# rf_front_lf.net
KiCad netlist of a schematic drawn in EAGLE
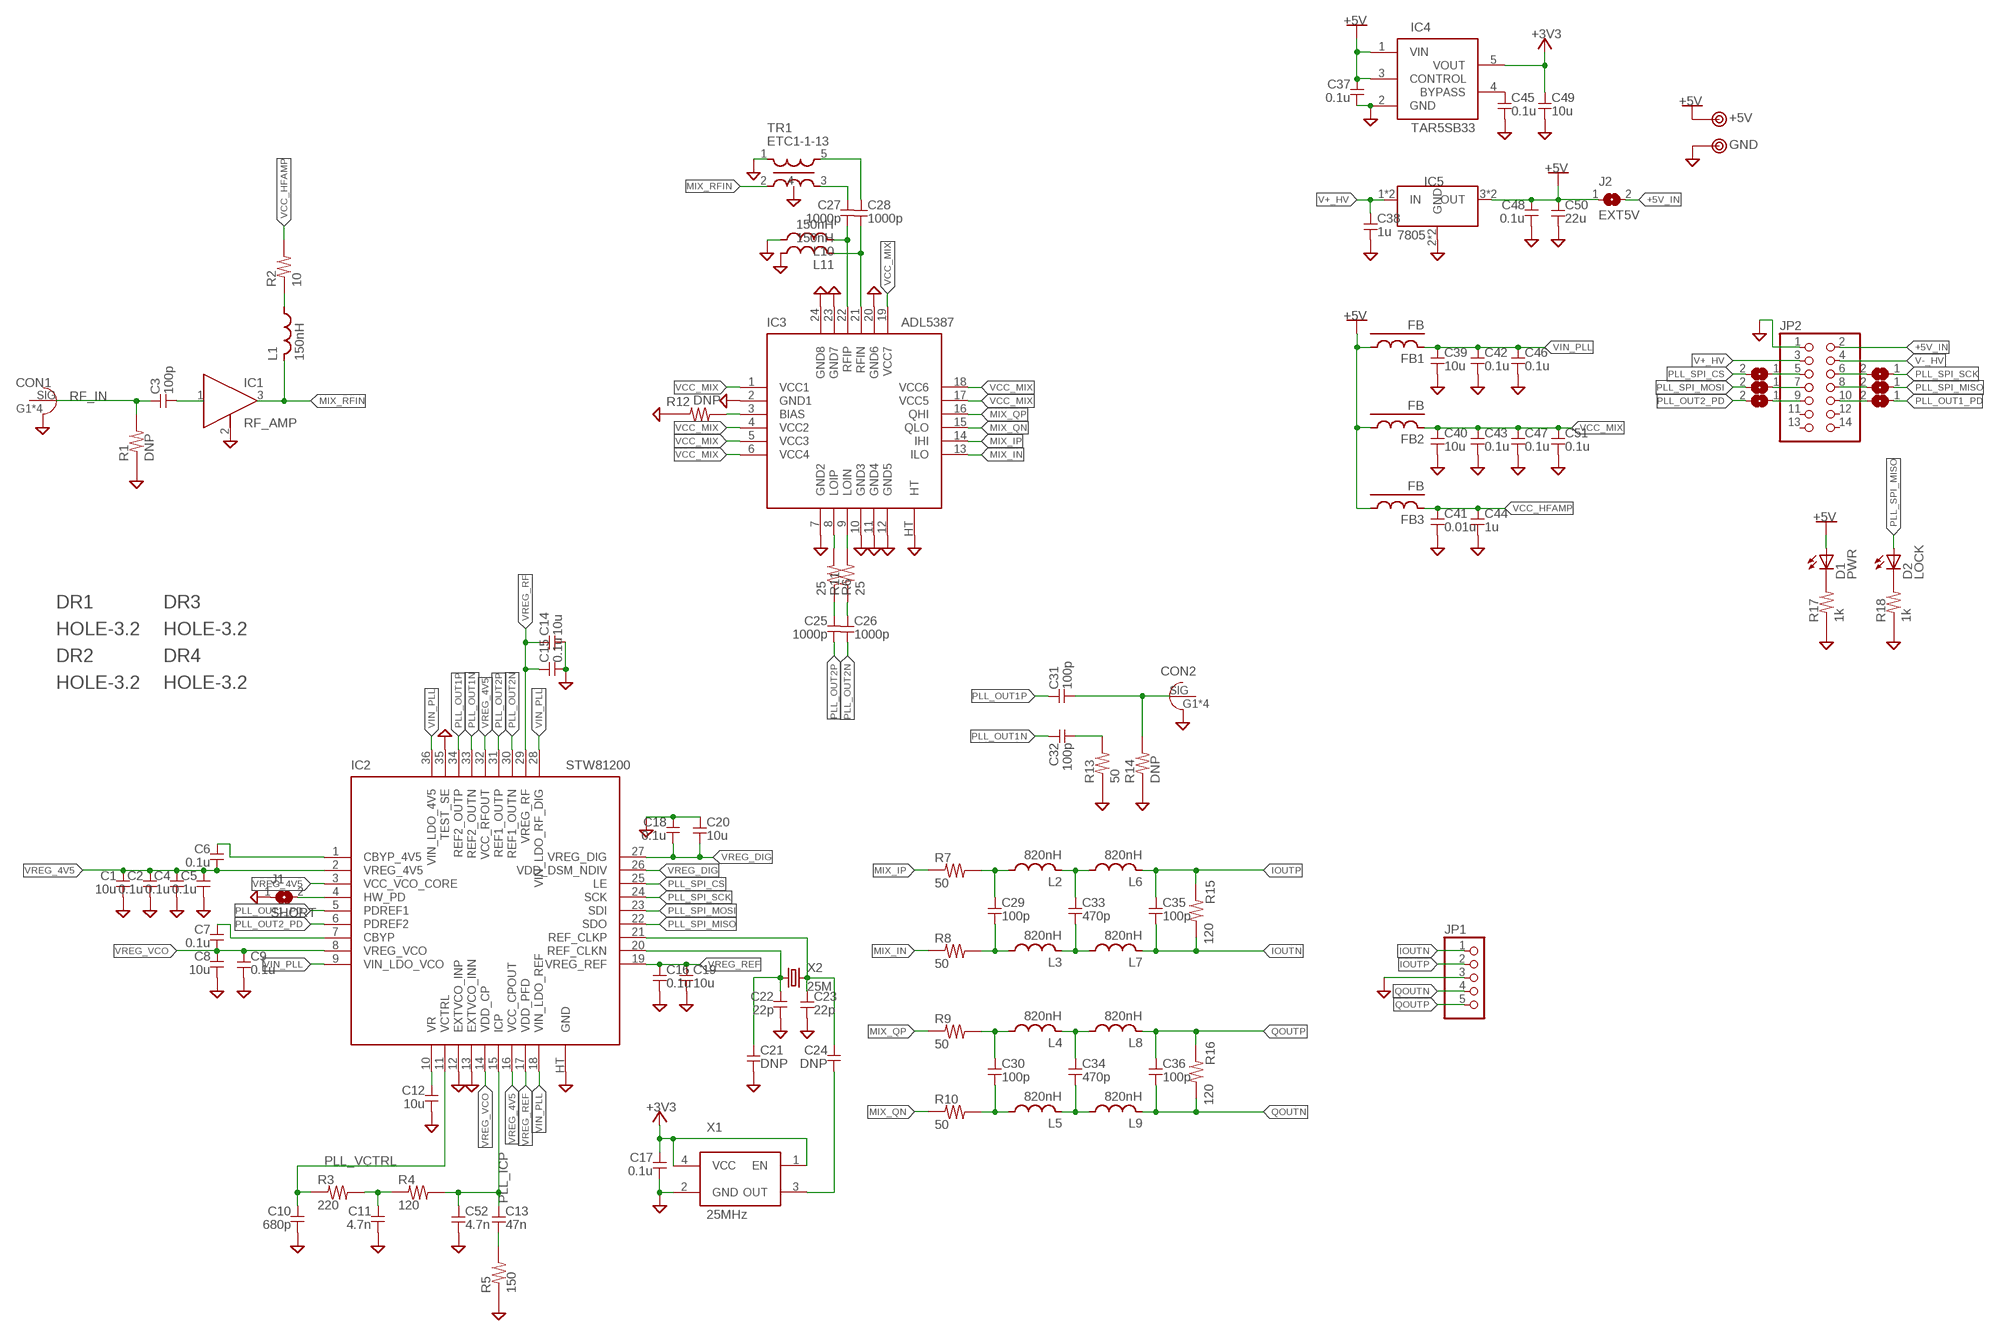
[diagram p0: schematic, sheet 1]

(export (version "E")
  (design (tool "Eeschema 10.0.6"))
  (components
    (comp (ref "C1")
      (value "10u")
      (footprint "eagle-import:1608")
      (libsource (lib "eagle-import") (part "C-1608"))
    )
    (comp (ref "C2")
      (value "0.1u")
      (footprint "eagle-import:1608")
      (libsource (lib "eagle-import") (part "C-1608"))
    )
    (comp (ref "C3")
      (value "100p")
      (footprint "eagle-import:1608")
      (libsource (lib "eagle-import") (part "C-1608"))
    )
    (comp (ref "C4")
      (value "0.1u")
      (footprint "eagle-import:1608")
      (libsource (lib "eagle-import") (part "C-1608"))
    )
    (comp (ref "C5")
      (value "0.1u")
      (footprint "eagle-import:1608")
      (libsource (lib "eagle-import") (part "C-1608"))
    )
    (comp (ref "C6")
      (value "0.1u")
      (footprint "eagle-import:1608")
      (libsource (lib "eagle-import") (part "C-1608"))
    )
    (comp (ref "C7")
      (value "0.1u")
      (footprint "eagle-import:1608")
      (libsource (lib "eagle-import") (part "C-1608"))
    )
    (comp (ref "C8")
      (value "10u")
      (footprint "eagle-import:1608")
      (libsource (lib "eagle-import") (part "C-1608"))
    )
    (comp (ref "C9")
      (value "0.1u")
      (footprint "eagle-import:1608")
      (libsource (lib "eagle-import") (part "C-1608"))
    )
    (comp (ref "C10")
      (value "680p")
      (footprint "eagle-import:1608")
      (libsource (lib "eagle-import") (part "C-1608"))
    )
    (comp (ref "C11")
      (value "4.7n")
      (footprint "eagle-import:1608")
      (libsource (lib "eagle-import") (part "C-1608"))
    )
    (comp (ref "C12")
      (value "10u")
      (footprint "eagle-import:1608")
      (libsource (lib "eagle-import") (part "C-1608"))
    )
    (comp (ref "C13")
      (value "47n")
      (footprint "eagle-import:1608")
      (libsource (lib "eagle-import") (part "C-1608"))
    )
    (comp (ref "C14")
      (value "10u")
      (footprint "eagle-import:1608")
      (libsource (lib "eagle-import") (part "C-1608"))
    )
    (comp (ref "C15")
      (value "0.1u")
      (footprint "eagle-import:1608")
      (libsource (lib "eagle-import") (part "C-1608"))
    )
    (comp (ref "C16")
      (value "0.1u")
      (footprint "eagle-import:1608")
      (libsource (lib "eagle-import") (part "C-1608"))
    )
    (comp (ref "C17")
      (value "0.1u")
      (footprint "eagle-import:1608")
      (libsource (lib "eagle-import") (part "C-1608"))
    )
    (comp (ref "C18")
      (value "0.1u")
      (footprint "eagle-import:1608")
      (libsource (lib "eagle-import") (part "C-1608"))
    )
    (comp (ref "C19")
      (value "10u")
      (footprint "eagle-import:1608")
      (libsource (lib "eagle-import") (part "C-1608"))
    )
    (comp (ref "C20")
      (value "10u")
      (footprint "eagle-import:1608")
      (libsource (lib "eagle-import") (part "C-1608"))
    )
    (comp (ref "C21")
      (value "DNP")
      (footprint "eagle-import:1608")
      (libsource (lib "eagle-import") (part "C-1608"))
    )
    (comp (ref "C22")
      (value "22p")
      (footprint "eagle-import:1608")
      (libsource (lib "eagle-import") (part "C-1608"))
    )
    (comp (ref "C23")
      (value "22p")
      (footprint "eagle-import:1608")
      (libsource (lib "eagle-import") (part "C-1608"))
    )
    (comp (ref "C24")
      (value "DNP")
      (footprint "eagle-import:1608")
      (libsource (lib "eagle-import") (part "C-1608"))
    )
    (comp (ref "C25")
      (value "1000p")
      (footprint "eagle-import:1608")
      (libsource (lib "eagle-import") (part "C-1608"))
    )
    (comp (ref "C26")
      (value "1000p")
      (footprint "eagle-import:1608")
      (libsource (lib "eagle-import") (part "C-1608"))
    )
    (comp (ref "C27")
      (value "1000p")
      (footprint "eagle-import:1608")
      (libsource (lib "eagle-import") (part "C-1608"))
    )
    (comp (ref "C28")
      (value "1000p")
      (footprint "eagle-import:1608")
      (libsource (lib "eagle-import") (part "C-1608"))
    )
    (comp (ref "C29")
      (value "100p")
      (footprint "eagle-import:1608")
      (libsource (lib "eagle-import") (part "C-1608"))
    )
    (comp (ref "C30")
      (value "100p")
      (footprint "eagle-import:1608")
      (libsource (lib "eagle-import") (part "C-1608"))
    )
    (comp (ref "C31")
      (value "100p")
      (footprint "eagle-import:1608")
      (libsource (lib "eagle-import") (part "C-1608"))
    )
    (comp (ref "C32")
      (value "100p")
      (footprint "eagle-import:1608")
      (libsource (lib "eagle-import") (part "C-1608"))
    )
    (comp (ref "C33")
      (value "470p")
      (footprint "eagle-import:1608")
      (libsource (lib "eagle-import") (part "C-1608"))
    )
    (comp (ref "C34")
      (value "470p")
      (footprint "eagle-import:1608")
      (libsource (lib "eagle-import") (part "C-1608"))
    )
    (comp (ref "C35")
      (value "100p")
      (footprint "eagle-import:1608")
      (libsource (lib "eagle-import") (part "C-1608"))
    )
    (comp (ref "C36")
      (value "100p")
      (footprint "eagle-import:1608")
      (libsource (lib "eagle-import") (part "C-1608"))
    )
    (comp (ref "C37")
      (value "0.1u")
      (footprint "eagle-import:1608")
      (libsource (lib "eagle-import") (part "C-1608"))
    )
    (comp (ref "C38")
      (value "1u")
      (footprint "eagle-import:1608")
      (libsource (lib "eagle-import") (part "C-1608"))
    )
    (comp (ref "C39")
      (value "10u")
      (footprint "eagle-import:2012")
      (libsource (lib "eagle-import") (part "C-2012"))
    )
    (comp (ref "C40")
      (value "10u")
      (footprint "eagle-import:2012")
      (libsource (lib "eagle-import") (part "C-2012"))
    )
    (comp (ref "C41")
      (value "0.01u")
      (footprint "eagle-import:1608")
      (libsource (lib "eagle-import") (part "C-1608"))
    )
    (comp (ref "C42")
      (value "0.1u")
      (footprint "eagle-import:1608")
      (libsource (lib "eagle-import") (part "C-1608"))
    )
    (comp (ref "C43")
      (value "0.1u")
      (footprint "eagle-import:1608")
      (libsource (lib "eagle-import") (part "C-1608"))
    )
    (comp (ref "C44")
      (value "1u")
      (footprint "eagle-import:1608")
      (libsource (lib "eagle-import") (part "C-1608"))
    )
    (comp (ref "C45")
      (value "0.1u")
      (footprint "eagle-import:1608")
      (libsource (lib "eagle-import") (part "C-1608"))
    )
    (comp (ref "C46")
      (value "0.1u")
      (footprint "eagle-import:1608")
      (libsource (lib "eagle-import") (part "C-1608"))
    )
    (comp (ref "C47")
      (value "0.1u")
      (footprint "eagle-import:1608")
      (libsource (lib "eagle-import") (part "C-1608"))
    )
    (comp (ref "C48")
      (value "0.1u")
      (footprint "eagle-import:1608")
      (libsource (lib "eagle-import") (part "C-1608"))
    )
    (comp (ref "C49")
      (value "10u")
      (footprint "eagle-import:1608")
      (libsource (lib "eagle-import") (part "C-1608"))
    )
    (comp (ref "C50")
      (value "22u")
      (footprint "eagle-import:3225")
      (libsource (lib "eagle-import") (part "C-3225"))
    )
    (comp (ref "C51")
      (value "0.1u")
      (footprint "eagle-import:1608")
      (libsource (lib "eagle-import") (part "C-1608"))
    )
    (comp (ref "C52")
      (value "4.7n")
      (footprint "eagle-import:1608")
      (libsource (lib "eagle-import") (part "C-1608"))
    )
    (comp (ref "CON1")
      (value "RF_IN")
      (footprint "eagle-import:SMA-EDGE")
      (libsource (lib "eagle-import") (part "SMA-142-0701-801"))
    )
    (comp (ref "CON2")
      (value "PLL_OUT")
      (footprint "eagle-import:SMA-EDGE")
      (libsource (lib "eagle-import") (part "SMA-142-0701-801"))
    )
    (comp (ref "D1")
      (value "PWR")
      (footprint "eagle-import:D1608")
      (libsource (lib "eagle-import") (part "LED-SMD1608"))
    )
    (comp (ref "D2")
      (value "LOCK")
      (footprint "eagle-import:D1608")
      (libsource (lib "eagle-import") (part "LED-SMD1608"))
    )
    (comp (ref "DR1")
      (value "HOLE-3.2")
      (footprint "eagle-import:HOLE_3.2")
      (libsource (lib "eagle-import") (part "HOLE-3.2"))
    )
    (comp (ref "DR2")
      (value "HOLE-3.2")
      (footprint "eagle-import:HOLE_3.2")
      (libsource (lib "eagle-import") (part "HOLE-3.2"))
    )
    (comp (ref "DR3")
      (value "HOLE-3.2")
      (footprint "eagle-import:HOLE_3.2")
      (libsource (lib "eagle-import") (part "HOLE-3.2"))
    )
    (comp (ref "DR4")
      (value "HOLE-3.2")
      (footprint "eagle-import:HOLE_3.2")
      (libsource (lib "eagle-import") (part "HOLE-3.2"))
    )
    (comp (ref "FB1")
      (value "FB")
      (footprint "eagle-import:1608-J")
      (libsource (lib "eagle-import") (part "FB"))
    )
    (comp (ref "FB2")
      (value "FB")
      (footprint "eagle-import:1608-J")
      (libsource (lib "eagle-import") (part "FB"))
    )
    (comp (ref "FB3")
      (value "FB")
      (footprint "eagle-import:1608-J")
      (libsource (lib "eagle-import") (part "FB"))
    )
    (comp (ref "IC1")
      (value "RF_AMP")
      (footprint "eagle-import:SOT89")
      (libsource (lib "eagle-import") (part "RF_AMP"))
    )
    (comp (ref "IC2")
      (value "STW81200")
      (footprint "eagle-import:VFQFPN36")
      (libsource (lib "eagle-import") (part "STW81200"))
    )
    (comp (ref "IC3")
      (value "ADL5387")
      (footprint "eagle-import:LFCSP24")
      (libsource (lib "eagle-import") (part "ADL5387"))
    )
    (comp (ref "IC4")
      (value "TAR5SB33")
      (footprint "eagle-import:SOT23-5")
      (libsource (lib "eagle-import") (part "TAR5SB33"))
    )
    (comp (ref "IC5")
      (value "7805")
      (footprint "eagle-import:TO220-SOP-DUAL")
      (libsource (lib "eagle-import") (part "78X-3"))
    )
    (comp (ref "J1")
      (value "SHORT")
      (footprint "eagle-import:1608-J")
      (libsource (lib "eagle-import") (part "SJ-1608"))
    )
    (comp (ref "J2")
      (value "EXT5V")
      (footprint "eagle-import:1608-J")
      (libsource (lib "eagle-import") (part "SJ-1608"))
    )
    (comp (ref "J3")
      (value "CS")
      (footprint "eagle-import:1608-J")
      (libsource (lib "eagle-import") (part "SJ-1608"))
    )
    (comp (ref "J4")
      (value "MOSI")
      (footprint "eagle-import:1608-J")
      (libsource (lib "eagle-import") (part "SJ-1608"))
    )
    (comp (ref "J5")
      (value "PD2")
      (footprint "eagle-import:1608-J")
      (libsource (lib "eagle-import") (part "SJ-1608"))
    )
    (comp (ref "J6")
      (value "SCK")
      (footprint "eagle-import:1608-J")
      (libsource (lib "eagle-import") (part "SJ-1608"))
    )
    (comp (ref "J7")
      (value "MISO")
      (footprint "eagle-import:1608-J")
      (libsource (lib "eagle-import") (part "SJ-1608"))
    )
    (comp (ref "J8")
      (value "PD1")
      (footprint "eagle-import:1608-J")
      (libsource (lib "eagle-import") (part "SJ-1608"))
    )
    (comp (ref "JP1")
      (value "PINHD-1X5")
      (footprint "eagle-import:1X05")
      (libsource (lib "eagle-import") (part "PINHD-1X5"))
    )
    (comp (ref "JP2")
      (value "PINHD-2X7")
      (footprint "eagle-import:2X07")
      (libsource (lib "eagle-import") (part "PINHD-2X7"))
    )
    (comp (ref "L1")
      (value "150nH")
      (footprint "eagle-import:1608")
      (libsource (lib "eagle-import") (part "L-1608"))
    )
    (comp (ref "L2")
      (value "820nH")
      (footprint "eagle-import:1608")
      (libsource (lib "eagle-import") (part "L-1608"))
    )
    (comp (ref "L3")
      (value "820nH")
      (footprint "eagle-import:1608")
      (libsource (lib "eagle-import") (part "L-1608"))
    )
    (comp (ref "L4")
      (value "820nH")
      (footprint "eagle-import:1608")
      (libsource (lib "eagle-import") (part "L-1608"))
    )
    (comp (ref "L5")
      (value "820nH")
      (footprint "eagle-import:1608")
      (libsource (lib "eagle-import") (part "L-1608"))
    )
    (comp (ref "L6")
      (value "820nH")
      (footprint "eagle-import:1608")
      (libsource (lib "eagle-import") (part "L-1608"))
    )
    (comp (ref "L7")
      (value "820nH")
      (footprint "eagle-import:1608")
      (libsource (lib "eagle-import") (part "L-1608"))
    )
    (comp (ref "L8")
      (value "820nH")
      (footprint "eagle-import:1608")
      (libsource (lib "eagle-import") (part "L-1608"))
    )
    (comp (ref "L9")
      (value "820nH")
      (footprint "eagle-import:1608")
      (libsource (lib "eagle-import") (part "L-1608"))
    )
    (comp (ref "L10")
      (value "150nH")
      (footprint "eagle-import:1608")
      (libsource (lib "eagle-import") (part "L-1608"))
    )
    (comp (ref "L11")
      (value "150nH")
      (footprint "eagle-import:1608")
      (libsource (lib "eagle-import") (part "L-1608"))
    )
    (comp (ref "R1")
      (value "DNP")
      (footprint "eagle-import:1608")
      (libsource (lib "eagle-import") (part "R-1608"))
    )
    (comp (ref "R2")
      (value "10")
      (footprint "eagle-import:1608")
      (libsource (lib "eagle-import") (part "R-1608"))
    )
    (comp (ref "R3")
      (value "220")
      (footprint "eagle-import:1608")
      (libsource (lib "eagle-import") (part "R-1608"))
    )
    (comp (ref "R4")
      (value "120")
      (footprint "eagle-import:1608")
      (libsource (lib "eagle-import") (part "R-1608"))
    )
    (comp (ref "R5")
      (value "150")
      (footprint "eagle-import:1608")
      (libsource (lib "eagle-import") (part "R-1608"))
    )
    (comp (ref "R6")
      (value "25")
      (footprint "eagle-import:1608")
      (libsource (lib "eagle-import") (part "R-1608"))
    )
    (comp (ref "R7")
      (value "50")
      (footprint "eagle-import:1608")
      (libsource (lib "eagle-import") (part "R-1608"))
    )
    (comp (ref "R8")
      (value "50")
      (footprint "eagle-import:1608")
      (libsource (lib "eagle-import") (part "R-1608"))
    )
    (comp (ref "R9")
      (value "50")
      (footprint "eagle-import:1608")
      (libsource (lib "eagle-import") (part "R-1608"))
    )
    (comp (ref "R10")
      (value "50")
      (footprint "eagle-import:1608")
      (libsource (lib "eagle-import") (part "R-1608"))
    )
    (comp (ref "R11")
      (value "25")
      (footprint "eagle-import:1608")
      (libsource (lib "eagle-import") (part "R-1608"))
    )
    (comp (ref "R12")
      (value "DNP")
      (footprint "eagle-import:1608")
      (libsource (lib "eagle-import") (part "R-1608"))
    )
    (comp (ref "R13")
      (value "50")
      (footprint "eagle-import:1608")
      (libsource (lib "eagle-import") (part "R-1608"))
    )
    (comp (ref "R14")
      (value "DNP")
      (footprint "eagle-import:1608")
      (libsource (lib "eagle-import") (part "R-1608"))
    )
    (comp (ref "R15")
      (value "120")
      (footprint "eagle-import:1608")
      (libsource (lib "eagle-import") (part "R-1608"))
    )
    (comp (ref "R16")
      (value "120")
      (footprint "eagle-import:1608")
      (libsource (lib "eagle-import") (part "R-1608"))
    )
    (comp (ref "R17")
      (value "1k")
      (footprint "eagle-import:1608")
      (libsource (lib "eagle-import") (part "R-1608"))
    )
    (comp (ref "R18")
      (value "1k")
      (footprint "eagle-import:1608")
      (libsource (lib "eagle-import") (part "R-1608"))
    )
    (comp (ref "TP1")
      (value "+5V")
      (footprint "eagle-import:TESTPIN")
      (libsource (lib "eagle-import") (part "TESTPIN"))
    )
    (comp (ref "TP2")
      (value "GND")
      (footprint "eagle-import:TESTPIN")
      (libsource (lib "eagle-import") (part "TESTPIN"))
    )
    (comp (ref "TR1")
      (value "ETC1-1-13")
      (footprint "eagle-import:ETC1-1-13")
      (libsource (lib "eagle-import") (part "ETC1-1-13"))
    )
    (comp (ref "X1")
      (value "25MHz")
      (footprint "eagle-import:KC3225")
      (libsource (lib "eagle-import") (part "OSC-KC3225"))
    )
    (comp (ref "X2")
      (value "25M")
      (footprint "eagle-import:HC49_S")
      (libsource (lib "eagle-import") (part "CRYSTALHC49S"))
    )
  )
  (nets
    (net (code "1") (name "+3V3") (class "Default")
      (node (ref "C17") (pin "1") (pinfunction "1_1") (pintype "passive"))
      (node (ref "C49") (pin "1") (pinfunction "1_1") (pintype "passive"))
      (node (ref "IC4") (pin "5") (pinfunction "VOUT_5") (pintype "power_in"))
      (node (ref "X1") (pin "1") (pinfunction "EN_1") (pintype "input"))
      (node (ref "X1") (pin "4") (pinfunction "VCC_4") (pintype "power_in"))
    )
    (net (code "2") (name "+5V") (class "Default")
      (node (ref "C37") (pin "1") (pinfunction "1_1") (pintype "passive"))
      (node (ref "C48") (pin "1") (pinfunction "1_1") (pintype "passive"))
      (node (ref "C50") (pin "1") (pinfunction "1_1") (pintype "passive"))
      (node (ref "D1") (pin "A") (pinfunction "A_A") (pintype "passive"))
      (node (ref "FB1") (pin "1") (pinfunction "1_1") (pintype "passive"))
      (node (ref "FB2") (pin "1") (pinfunction "1_1") (pintype "passive"))
      (node (ref "FB3") (pin "1") (pinfunction "1_1") (pintype "passive"))
      (node (ref "IC4") (pin "1") (pinfunction "VIN_1") (pintype "power_in"))
      (node (ref "IC4") (pin "3") (pinfunction "CONTROL_3") (pintype "input"))
      (node (ref "IC5") (pin "3") (pinfunction "OUT_3") (pintype "output"))
      (node (ref "IC5") (pin "6") (pinfunction "OUT_6") (pintype "output"))
      (node (ref "J2") (pin "1") (pinfunction "1_1") (pintype "passive"))
      (node (ref "TP1") (pin "1") (pinfunction "1_1") (pintype "passive"))
    )
    (net (code "3") (name "+5V_IN") (class "Default")
      (node (ref "J2") (pin "2") (pinfunction "2_2") (pintype "passive"))
      (node (ref "JP2") (pin "2") (pinfunction "2_2") (pintype "passive"))
    )
    (net (code "4") (name "/PLL_ICP") (class "Default")
      (node (ref "C13") (pin "1") (pinfunction "1_1") (pintype "passive"))
      (node (ref "C52") (pin "1") (pinfunction "1_1") (pintype "passive"))
      (node (ref "IC2") (pin "15") (pinfunction "ICP_15") (pintype "output"))
      (node (ref "R4") (pin "2") (pinfunction "2_2") (pintype "passive"))
    )
    (net (code "5") (name "/PLL_VCTRL") (class "Default")
      (node (ref "C10") (pin "1") (pinfunction "1_1") (pintype "passive"))
      (node (ref "IC2") (pin "11") (pinfunction "VCTRL_11") (pintype "passive"))
      (node (ref "R3") (pin "1") (pinfunction "1_1") (pintype "passive"))
    )
    (net (code "6") (name "/RF_IN") (class "Default")
      (node (ref "C3") (pin "1") (pinfunction "1_1") (pintype "passive"))
      (node (ref "CON1") (pin "SIG") (pinfunction "SIG_SIG") (pintype "passive"))
      (node (ref "R1") (pin "2") (pinfunction "2_2") (pintype "passive"))
    )
    (net (code "7") (name "GND") (class "Default")
      (node (ref "C1") (pin "2") (pinfunction "2_2") (pintype "passive"))
      (node (ref "C10") (pin "2") (pinfunction "2_2") (pintype "passive"))
      (node (ref "C11") (pin "2") (pinfunction "2_2") (pintype "passive"))
      (node (ref "C12") (pin "2") (pinfunction "2_2") (pintype "passive"))
      (node (ref "C14") (pin "2") (pinfunction "2_2") (pintype "passive"))
      (node (ref "C15") (pin "2") (pinfunction "2_2") (pintype "passive"))
      (node (ref "C16") (pin "2") (pinfunction "2_2") (pintype "passive"))
      (node (ref "C17") (pin "2") (pinfunction "2_2") (pintype "passive"))
      (node (ref "C18") (pin "1") (pinfunction "1_1") (pintype "passive"))
      (node (ref "C19") (pin "2") (pinfunction "2_2") (pintype "passive"))
      (node (ref "C2") (pin "2") (pinfunction "2_2") (pintype "passive"))
      (node (ref "C20") (pin "1") (pinfunction "1_1") (pintype "passive"))
      (node (ref "C21") (pin "2") (pinfunction "2_2") (pintype "passive"))
      (node (ref "C22") (pin "2") (pinfunction "2_2") (pintype "passive"))
      (node (ref "C23") (pin "2") (pinfunction "2_2") (pintype "passive"))
      (node (ref "C37") (pin "2") (pinfunction "2_2") (pintype "passive"))
      (node (ref "C38") (pin "2") (pinfunction "2_2") (pintype "passive"))
      (node (ref "C39") (pin "2") (pinfunction "2_2") (pintype "passive"))
      (node (ref "C4") (pin "2") (pinfunction "2_2") (pintype "passive"))
      (node (ref "C40") (pin "2") (pinfunction "2_2") (pintype "passive"))
      (node (ref "C41") (pin "2") (pinfunction "2_2") (pintype "passive"))
      (node (ref "C42") (pin "2") (pinfunction "2_2") (pintype "passive"))
      (node (ref "C43") (pin "2") (pinfunction "2_2") (pintype "passive"))
      (node (ref "C44") (pin "2") (pinfunction "2_2") (pintype "passive"))
      (node (ref "C45") (pin "2") (pinfunction "2_2") (pintype "passive"))
      (node (ref "C46") (pin "2") (pinfunction "2_2") (pintype "passive"))
      (node (ref "C47") (pin "2") (pinfunction "2_2") (pintype "passive"))
      (node (ref "C48") (pin "2") (pinfunction "2_2") (pintype "passive"))
      (node (ref "C49") (pin "2") (pinfunction "2_2") (pintype "passive"))
      (node (ref "C5") (pin "2") (pinfunction "2_2") (pintype "passive"))
      (node (ref "C50") (pin "2") (pinfunction "2_2") (pintype "passive"))
      (node (ref "C51") (pin "2") (pinfunction "2_2") (pintype "passive"))
      (node (ref "C52") (pin "2") (pinfunction "2_2") (pintype "passive"))
      (node (ref "C8") (pin "2") (pinfunction "2_2") (pintype "passive"))
      (node (ref "C9") (pin "2") (pinfunction "2_2") (pintype "passive"))
      (node (ref "CON1") (pin "G1") (pinfunction "GND_G1") (pintype "passive"))
      (node (ref "CON1") (pin "G2") (pinfunction "GND_G2") (pintype "passive"))
      (node (ref "CON1") (pin "G3") (pinfunction "GND_G3") (pintype "passive"))
      (node (ref "CON1") (pin "G4") (pinfunction "GND_G4") (pintype "passive"))
      (node (ref "CON2") (pin "G1") (pinfunction "GND_G1") (pintype "passive"))
      (node (ref "CON2") (pin "G2") (pinfunction "GND_G2") (pintype "passive"))
      (node (ref "CON2") (pin "G3") (pinfunction "GND_G3") (pintype "passive"))
      (node (ref "CON2") (pin "G4") (pinfunction "GND_G4") (pintype "passive"))
      (node (ref "IC1") (pin "2") (pinfunction "GND_2") (pintype "power_in"))
      (node (ref "IC2") (pin "12") (pinfunction "EXTVCO_INP_12") (pintype "input"))
      (node (ref "IC2") (pin "13") (pinfunction "EXTVCO_INN_13") (pintype "input"))
      (node (ref "IC2") (pin "35") (pinfunction "TEST_SE_35") (pintype "input"))
      (node (ref "IC2") (pin "HT") (pinfunction "GND_HT") (pintype "power_in"))
      (node (ref "IC3") (pin "10") (pinfunction "GND3_10") (pintype "power_in"))
      (node (ref "IC3") (pin "11") (pinfunction "GND4_11") (pintype "power_in"))
      (node (ref "IC3") (pin "12") (pinfunction "GND5_12") (pintype "power_in"))
      (node (ref "IC3") (pin "2") (pinfunction "GND1_2") (pintype "power_in"))
      (node (ref "IC3") (pin "20") (pinfunction "GND6_20") (pintype "power_in"))
      (node (ref "IC3") (pin "23") (pinfunction "GND7_23") (pintype "power_in"))
      (node (ref "IC3") (pin "24") (pinfunction "GND8_24") (pintype "power_in"))
      (node (ref "IC3") (pin "7") (pinfunction "GND2_7") (pintype "power_in"))
      (node (ref "IC3") (pin "HT") (pinfunction "HT_HT") (pintype "passive"))
      (node (ref "IC4") (pin "2") (pinfunction "GND_2") (pintype "power_in"))
      (node (ref "IC5") (pin "2") (pinfunction "GND_2") (pintype "power_in"))
      (node (ref "IC5") (pin "5") (pinfunction "GND_5") (pintype "power_in"))
      (node (ref "J1") (pin "1") (pinfunction "1_1") (pintype "passive"))
      (node (ref "JP1") (pin "3") (pinfunction "3_3") (pintype "passive"))
      (node (ref "JP2") (pin "1") (pinfunction "1_1") (pintype "passive"))
      (node (ref "L10") (pin "1") (pinfunction "1_1") (pintype "passive"))
      (node (ref "L11") (pin "1") (pinfunction "1_1") (pintype "passive"))
      (node (ref "R1") (pin "1") (pinfunction "1_1") (pintype "passive"))
      (node (ref "R12") (pin "1") (pinfunction "1_1") (pintype "passive"))
      (node (ref "R13") (pin "1") (pinfunction "1_1") (pintype "passive"))
      (node (ref "R14") (pin "1") (pinfunction "1_1") (pintype "passive"))
      (node (ref "R17") (pin "1") (pinfunction "1_1") (pintype "passive"))
      (node (ref "R18") (pin "1") (pinfunction "1_1") (pintype "passive"))
      (node (ref "R5") (pin "1") (pinfunction "1_1") (pintype "passive"))
      (node (ref "TP2") (pin "1") (pinfunction "1_1") (pintype "passive"))
      (node (ref "TR1") (pin "1") (pinfunction "1_1") (pintype "passive"))
      (node (ref "TR1") (pin "4") (pinfunction "4_4") (pintype "passive"))
      (node (ref "X1") (pin "2") (pinfunction "GND_2") (pintype "power_in"))
    )
    (net (code "8") (name "IOUTN") (class "Default")
      (node (ref "C35") (pin "2") (pinfunction "2_2") (pintype "passive"))
      (node (ref "JP1") (pin "1") (pinfunction "1_1") (pintype "passive"))
      (node (ref "L7") (pin "2") (pinfunction "2_2") (pintype "passive"))
      (node (ref "R15") (pin "1") (pinfunction "1_1") (pintype "passive"))
    )
    (net (code "9") (name "IOUTP") (class "Default")
      (node (ref "C35") (pin "1") (pinfunction "1_1") (pintype "passive"))
      (node (ref "JP1") (pin "2") (pinfunction "2_2") (pintype "passive"))
      (node (ref "L6") (pin "2") (pinfunction "2_2") (pintype "passive"))
      (node (ref "R15") (pin "2") (pinfunction "2_2") (pintype "passive"))
    )
    (net (code "10") (name "MIX_IN") (class "Default")
      (node (ref "IC3") (pin "13") (pinfunction "ILO_13") (pintype "input"))
      (node (ref "R8") (pin "1") (pinfunction "1_1") (pintype "passive"))
    )
    (net (code "11") (name "MIX_IP") (class "Default")
      (node (ref "IC3") (pin "14") (pinfunction "IHI_14") (pintype "input"))
      (node (ref "R7") (pin "1") (pinfunction "1_1") (pintype "passive"))
    )
    (net (code "12") (name "MIX_QN") (class "Default")
      (node (ref "IC3") (pin "15") (pinfunction "QLO_15") (pintype "output"))
      (node (ref "R10") (pin "1") (pinfunction "1_1") (pintype "passive"))
    )
    (net (code "13") (name "MIX_QP") (class "Default")
      (node (ref "IC3") (pin "16") (pinfunction "QHI_16") (pintype "output"))
      (node (ref "R9") (pin "1") (pinfunction "1_1") (pintype "passive"))
    )
    (net (code "14") (name "MIX_RFIN") (class "Default")
      (node (ref "IC1") (pin "3") (pinfunction "OUT_3") (pintype "output"))
      (node (ref "L1") (pin "2") (pinfunction "2_2") (pintype "passive"))
      (node (ref "TR1") (pin "2") (pinfunction "2_2") (pintype "passive"))
    )
    (net (code "15") (name "Net-(C11-Pad1)") (class "Default")
      (node (ref "C11") (pin "1") (pinfunction "1_1") (pintype "passive"))
      (node (ref "R3") (pin "2") (pinfunction "2_2") (pintype "passive"))
      (node (ref "R4") (pin "1") (pinfunction "1_1") (pintype "passive"))
    )
    (net (code "16") (name "Net-(C13-Pad2)") (class "Default")
      (node (ref "C13") (pin "2") (pinfunction "2_2") (pintype "passive"))
      (node (ref "R5") (pin "2") (pinfunction "2_2") (pintype "passive"))
    )
    (net (code "17") (name "Net-(C25-Pad1)") (class "Default")
      (node (ref "C25") (pin "1") (pinfunction "1_1") (pintype "passive"))
      (node (ref "R6") (pin "1") (pinfunction "1_1") (pintype "passive"))
    )
    (net (code "18") (name "Net-(C26-Pad1)") (class "Default")
      (node (ref "C26") (pin "1") (pinfunction "1_1") (pintype "passive"))
      (node (ref "R11") (pin "1") (pinfunction "1_1") (pintype "passive"))
    )
    (net (code "19") (name "Net-(C27-Pad1)") (class "Default")
      (node (ref "C27") (pin "1") (pinfunction "1_1") (pintype "passive"))
      (node (ref "TR1") (pin "3") (pinfunction "3_3") (pintype "passive"))
    )
    (net (code "20") (name "Net-(C28-Pad1)") (class "Default")
      (node (ref "C28") (pin "1") (pinfunction "1_1") (pintype "passive"))
      (node (ref "TR1") (pin "5") (pinfunction "5_5") (pintype "passive"))
    )
    (net (code "21") (name "Net-(C29-Pad1)") (class "Default")
      (node (ref "C29") (pin "1") (pinfunction "1_1") (pintype "passive"))
      (node (ref "L2") (pin "1") (pinfunction "1_1") (pintype "passive"))
      (node (ref "R7") (pin "2") (pinfunction "2_2") (pintype "passive"))
    )
    (net (code "22") (name "Net-(C29-Pad2)") (class "Default")
      (node (ref "C29") (pin "2") (pinfunction "2_2") (pintype "passive"))
      (node (ref "L3") (pin "1") (pinfunction "1_1") (pintype "passive"))
      (node (ref "R8") (pin "2") (pinfunction "2_2") (pintype "passive"))
    )
    (net (code "23") (name "Net-(C30-Pad1)") (class "Default")
      (node (ref "C30") (pin "1") (pinfunction "1_1") (pintype "passive"))
      (node (ref "L4") (pin "1") (pinfunction "1_1") (pintype "passive"))
      (node (ref "R9") (pin "2") (pinfunction "2_2") (pintype "passive"))
    )
    (net (code "24") (name "Net-(C30-Pad2)") (class "Default")
      (node (ref "C30") (pin "2") (pinfunction "2_2") (pintype "passive"))
      (node (ref "L5") (pin "1") (pinfunction "1_1") (pintype "passive"))
      (node (ref "R10") (pin "2") (pinfunction "2_2") (pintype "passive"))
    )
    (net (code "25") (name "Net-(C31-Pad2)") (class "Default")
      (node (ref "C31") (pin "2") (pinfunction "2_2") (pintype "passive"))
      (node (ref "CON2") (pin "SIG") (pinfunction "SIG_SIG") (pintype "passive"))
      (node (ref "R14") (pin "2") (pinfunction "2_2") (pintype "passive"))
    )
    (net (code "26") (name "Net-(C32-Pad2)") (class "Default")
      (node (ref "C32") (pin "2") (pinfunction "2_2") (pintype "passive"))
      (node (ref "R13") (pin "2") (pinfunction "2_2") (pintype "passive"))
    )
    (net (code "27") (name "Net-(C33-Pad1)") (class "Default")
      (node (ref "C33") (pin "1") (pinfunction "1_1") (pintype "passive"))
      (node (ref "L2") (pin "2") (pinfunction "2_2") (pintype "passive"))
      (node (ref "L6") (pin "1") (pinfunction "1_1") (pintype "passive"))
    )
    (net (code "28") (name "Net-(C33-Pad2)") (class "Default")
      (node (ref "C33") (pin "2") (pinfunction "2_2") (pintype "passive"))
      (node (ref "L3") (pin "2") (pinfunction "2_2") (pintype "passive"))
      (node (ref "L7") (pin "1") (pinfunction "1_1") (pintype "passive"))
    )
    (net (code "29") (name "Net-(C34-Pad1)") (class "Default")
      (node (ref "C34") (pin "1") (pinfunction "1_1") (pintype "passive"))
      (node (ref "L4") (pin "2") (pinfunction "2_2") (pintype "passive"))
      (node (ref "L8") (pin "1") (pinfunction "1_1") (pintype "passive"))
    )
    (net (code "30") (name "Net-(C34-Pad2)") (class "Default")
      (node (ref "C34") (pin "2") (pinfunction "2_2") (pintype "passive"))
      (node (ref "L5") (pin "2") (pinfunction "2_2") (pintype "passive"))
      (node (ref "L9") (pin "1") (pinfunction "1_1") (pintype "passive"))
    )
    (net (code "31") (name "Net-(D1-PadK)") (class "Default")
      (node (ref "D1") (pin "K") (pinfunction "K_K") (pintype "passive"))
      (node (ref "R17") (pin "2") (pinfunction "2_2") (pintype "passive"))
    )
    (net (code "32") (name "Net-(D2-PadK)") (class "Default")
      (node (ref "D2") (pin "K") (pinfunction "K_K") (pintype "passive"))
      (node (ref "R18") (pin "2") (pinfunction "2_2") (pintype "passive"))
    )
    (net (code "33") (name "Net-(IC1-IN)") (class "Default")
      (node (ref "C3") (pin "2") (pinfunction "2_2") (pintype "passive"))
      (node (ref "IC1") (pin "1") (pinfunction "IN_1") (pintype "input"))
    )
    (net (code "34") (name "Net-(IC2-CBYP)") (class "Default")
      (node (ref "C7") (pin "1") (pinfunction "1_1") (pintype "passive"))
      (node (ref "IC2") (pin "7") (pinfunction "CBYP_7") (pintype "passive"))
    )
    (net (code "35") (name "Net-(IC2-CBYP_4V5)") (class "Default")
      (node (ref "C6") (pin "1") (pinfunction "1_1") (pintype "passive"))
      (node (ref "IC2") (pin "1") (pinfunction "CBYP_4V5_1") (pintype "passive"))
    )
    (net (code "36") (name "Net-(IC2-HW_PD)") (class "Default")
      (node (ref "IC2") (pin "4") (pinfunction "HW_PD_4") (pintype "input"))
      (node (ref "J1") (pin "2") (pinfunction "2_2") (pintype "passive"))
    )
    (net (code "37") (name "Net-(IC2-REF_CLKN)") (class "Default")
      (node (ref "C21") (pin "1") (pinfunction "1_1") (pintype "passive"))
      (node (ref "C22") (pin "1") (pinfunction "1_1") (pintype "passive"))
      (node (ref "IC2") (pin "20") (pinfunction "REF_CLKN_20") (pintype "input"))
      (node (ref "X2") (pin "1") (pinfunction "1_1") (pintype "passive"))
    )
    (net (code "38") (name "Net-(IC2-REF_CLKP)") (class "Default")
      (node (ref "C23") (pin "1") (pinfunction "1_1") (pintype "passive"))
      (node (ref "C24") (pin "1") (pinfunction "1_1") (pintype "passive"))
      (node (ref "IC2") (pin "21") (pinfunction "REF_CLKP_21") (pintype "input"))
      (node (ref "X2") (pin "2") (pinfunction "2_2") (pintype "passive"))
    )
    (net (code "39") (name "Net-(IC2-VR)") (class "Default")
      (node (ref "C12") (pin "1") (pinfunction "1_1") (pintype "passive"))
      (node (ref "IC2") (pin "10") (pinfunction "VR_10") (pintype "passive"))
    )
    (net (code "40") (name "Net-(IC3-BIAS)") (class "Default")
      (node (ref "IC3") (pin "3") (pinfunction "BIAS_3") (pintype "passive"))
      (node (ref "R12") (pin "2") (pinfunction "2_2") (pintype "passive"))
    )
    (net (code "41") (name "Net-(IC3-LOIN)") (class "Default")
      (node (ref "IC3") (pin "9") (pinfunction "LOIN_9") (pintype "input"))
      (node (ref "R11") (pin "2") (pinfunction "2_2") (pintype "passive"))
    )
    (net (code "42") (name "Net-(IC3-LOIP)") (class "Default")
      (node (ref "IC3") (pin "8") (pinfunction "LOIP_8") (pintype "input"))
      (node (ref "R6") (pin "2") (pinfunction "2_2") (pintype "passive"))
    )
    (net (code "43") (name "Net-(IC3-RFIN)") (class "Default")
      (node (ref "C28") (pin "2") (pinfunction "2_2") (pintype "passive"))
      (node (ref "IC3") (pin "21") (pinfunction "RFIN_21") (pintype "input"))
      (node (ref "L11") (pin "2") (pinfunction "2_2") (pintype "passive"))
    )
    (net (code "44") (name "Net-(IC3-RFIP)") (class "Default")
      (node (ref "C27") (pin "2") (pinfunction "2_2") (pintype "passive"))
      (node (ref "IC3") (pin "22") (pinfunction "RFIP_22") (pintype "input"))
      (node (ref "L10") (pin "2") (pinfunction "2_2") (pintype "passive"))
    )
    (net (code "45") (name "Net-(IC4-BYPASS)") (class "Default")
      (node (ref "C45") (pin "1") (pinfunction "1_1") (pintype "passive"))
      (node (ref "IC4") (pin "4") (pinfunction "BYPASS_4") (pintype "passive"))
    )
    (net (code "46") (name "Net-(J3-Pad1)") (class "Default")
      (node (ref "J3") (pin "1") (pinfunction "1_1") (pintype "passive"))
      (node (ref "JP2") (pin "5") (pinfunction "5_5") (pintype "passive"))
    )
    (net (code "47") (name "Net-(J4-Pad1)") (class "Default")
      (node (ref "J4") (pin "1") (pinfunction "1_1") (pintype "passive"))
      (node (ref "JP2") (pin "7") (pinfunction "7_7") (pintype "passive"))
    )
    (net (code "48") (name "Net-(J5-Pad1)") (class "Default")
      (node (ref "J5") (pin "1") (pinfunction "1_1") (pintype "passive"))
      (node (ref "JP2") (pin "9") (pinfunction "9_9") (pintype "passive"))
    )
    (net (code "49") (name "Net-(J6-Pad2)") (class "Default")
      (node (ref "J6") (pin "2") (pinfunction "2_2") (pintype "passive"))
      (node (ref "JP2") (pin "6") (pinfunction "6_6") (pintype "passive"))
    )
    (net (code "50") (name "Net-(J7-Pad2)") (class "Default")
      (node (ref "J7") (pin "2") (pinfunction "2_2") (pintype "passive"))
      (node (ref "JP2") (pin "8") (pinfunction "8_8") (pintype "passive"))
    )
    (net (code "51") (name "Net-(J8-Pad2)") (class "Default")
      (node (ref "J8") (pin "2") (pinfunction "2_2") (pintype "passive"))
      (node (ref "JP2") (pin "10") (pinfunction "10_10") (pintype "passive"))
    )
    (net (code "52") (name "Net-(L1-Pad1)") (class "Default")
      (node (ref "L1") (pin "1") (pinfunction "1_1") (pintype "passive"))
      (node (ref "R2") (pin "1") (pinfunction "1_1") (pintype "passive"))
    )
    (net (code "53") (name "Net-(X1-OUT)") (class "Default")
      (node (ref "C24") (pin "2") (pinfunction "2_2") (pintype "passive"))
      (node (ref "X1") (pin "3") (pinfunction "OUT_3") (pintype "output"))
    )
    (net (code "54") (name "PLL_OUT1N") (class "Default")
      (node (ref "C32") (pin "1") (pinfunction "1_1") (pintype "passive"))
      (node (ref "IC2") (pin "33") (pinfunction "REF2_OUTN_33") (pintype "passive"))
    )
    (net (code "55") (name "PLL_OUT1P") (class "Default")
      (node (ref "C31") (pin "1") (pinfunction "1_1") (pintype "passive"))
      (node (ref "IC2") (pin "34") (pinfunction "REF2_OUTP_34") (pintype "passive"))
    )
    (net (code "56") (name "PLL_OUT1_PD") (class "Default")
      (node (ref "IC2") (pin "5") (pinfunction "PDREF1_5") (pintype "input"))
      (node (ref "J8") (pin "1") (pinfunction "1_1") (pintype "passive"))
    )
    (net (code "57") (name "PLL_OUT2N") (class "Default")
      (node (ref "C26") (pin "2") (pinfunction "2_2") (pintype "passive"))
      (node (ref "IC2") (pin "30") (pinfunction "REF1_OUTN_30") (pintype "output"))
    )
    (net (code "58") (name "PLL_OUT2P") (class "Default")
      (node (ref "C25") (pin "2") (pinfunction "2_2") (pintype "passive"))
      (node (ref "IC2") (pin "31") (pinfunction "REF1_OUTP_31") (pintype "output"))
    )
    (net (code "59") (name "PLL_OUT2_PD") (class "Default")
      (node (ref "IC2") (pin "6") (pinfunction "PDREF2_6") (pintype "input"))
      (node (ref "J5") (pin "2") (pinfunction "2_2") (pintype "passive"))
    )
    (net (code "60") (name "PLL_SPI_CS") (class "Default")
      (node (ref "IC2") (pin "25") (pinfunction "LE_25") (pintype "bidirectional"))
      (node (ref "J3") (pin "2") (pinfunction "2_2") (pintype "passive"))
    )
    (net (code "61") (name "PLL_SPI_MISO") (class "Default")
      (node (ref "D2") (pin "A") (pinfunction "A_A") (pintype "passive"))
      (node (ref "IC2") (pin "22") (pinfunction "SDO_22") (pintype "bidirectional"))
      (node (ref "J7") (pin "1") (pinfunction "1_1") (pintype "passive"))
    )
    (net (code "62") (name "PLL_SPI_MOSI") (class "Default")
      (node (ref "IC2") (pin "23") (pinfunction "SDI_23") (pintype "bidirectional"))
      (node (ref "J4") (pin "2") (pinfunction "2_2") (pintype "passive"))
    )
    (net (code "63") (name "PLL_SPI_SCK") (class "Default")
      (node (ref "IC2") (pin "24") (pinfunction "SCK_24") (pintype "bidirectional"))
      (node (ref "J6") (pin "1") (pinfunction "1_1") (pintype "passive"))
    )
    (net (code "64") (name "QOUTN") (class "Default")
      (node (ref "C36") (pin "2") (pinfunction "2_2") (pintype "passive"))
      (node (ref "JP1") (pin "4") (pinfunction "4_4") (pintype "passive"))
      (node (ref "L9") (pin "2") (pinfunction "2_2") (pintype "passive"))
      (node (ref "R16") (pin "1") (pinfunction "1_1") (pintype "passive"))
    )
    (net (code "65") (name "QOUTP") (class "Default")
      (node (ref "C36") (pin "1") (pinfunction "1_1") (pintype "passive"))
      (node (ref "JP1") (pin "5") (pinfunction "5_5") (pintype "passive"))
      (node (ref "L8") (pin "2") (pinfunction "2_2") (pintype "passive"))
      (node (ref "R16") (pin "2") (pinfunction "2_2") (pintype "passive"))
    )
    (net (code "66") (name "V+_HV") (class "Default")
      (node (ref "C38") (pin "1") (pinfunction "1_1") (pintype "passive"))
      (node (ref "IC5") (pin "1") (pinfunction "IN_1") (pintype "power_in"))
      (node (ref "IC5") (pin "4") (pinfunction "IN_4") (pintype "power_in"))
      (node (ref "JP2") (pin "3") (pinfunction "3_3") (pintype "passive"))
    )
    (net (code "67") (name "V-_HV") (class "Default")
      (node (ref "JP2") (pin "4") (pinfunction "4_4") (pintype "passive"))
    )
    (net (code "68") (name "VCC_HFAMP") (class "Default")
      (node (ref "C41") (pin "1") (pinfunction "1_1") (pintype "passive"))
      (node (ref "C44") (pin "1") (pinfunction "1_1") (pintype "passive"))
      (node (ref "FB3") (pin "2") (pinfunction "2_2") (pintype "passive"))
      (node (ref "R2") (pin "2") (pinfunction "2_2") (pintype "passive"))
    )
    (net (code "69") (name "VCC_MIX") (class "Default")
      (node (ref "C40") (pin "1") (pinfunction "1_1") (pintype "passive"))
      (node (ref "C43") (pin "1") (pinfunction "1_1") (pintype "passive"))
      (node (ref "C47") (pin "1") (pinfunction "1_1") (pintype "passive"))
      (node (ref "C51") (pin "1") (pinfunction "1_1") (pintype "passive"))
      (node (ref "FB2") (pin "2") (pinfunction "2_2") (pintype "passive"))
      (node (ref "IC3") (pin "1") (pinfunction "VCC1_1") (pintype "power_in"))
      (node (ref "IC3") (pin "17") (pinfunction "VCC5_17") (pintype "power_in"))
      (node (ref "IC3") (pin "18") (pinfunction "VCC6_18") (pintype "power_in"))
      (node (ref "IC3") (pin "19") (pinfunction "VCC7_19") (pintype "power_in"))
      (node (ref "IC3") (pin "4") (pinfunction "VCC2_4") (pintype "power_in"))
      (node (ref "IC3") (pin "5") (pinfunction "VCC3_5") (pintype "power_in"))
      (node (ref "IC3") (pin "6") (pinfunction "VCC4_6") (pintype "power_in"))
    )
    (net (code "70") (name "VIN_PLL") (class "Default")
      (node (ref "C39") (pin "1") (pinfunction "1_1") (pintype "passive"))
      (node (ref "C42") (pin "1") (pinfunction "1_1") (pintype "passive"))
      (node (ref "C46") (pin "1") (pinfunction "1_1") (pintype "passive"))
      (node (ref "FB1") (pin "2") (pinfunction "2_2") (pintype "passive"))
      (node (ref "IC2") (pin "18") (pinfunction "VIN_LDO_REF_18") (pintype "power_in"))
      (node (ref "IC2") (pin "28") (pinfunction "VIN_LDO_RF_DIG_28") (pintype "power_in"))
      (node (ref "IC2") (pin "36") (pinfunction "VIN_LDO_4V5_36") (pintype "power_in"))
      (node (ref "IC2") (pin "9") (pinfunction "VIN_LDO_VCO_9") (pintype "power_in"))
    )
    (net (code "71") (name "VREG_4V5") (class "Default")
      (node (ref "C1") (pin "1") (pinfunction "1_1") (pintype "passive"))
      (node (ref "C2") (pin "1") (pinfunction "1_1") (pintype "passive"))
      (node (ref "C4") (pin "1") (pinfunction "1_1") (pintype "passive"))
      (node (ref "C5") (pin "1") (pinfunction "1_1") (pintype "passive"))
      (node (ref "C6") (pin "2") (pinfunction "2_2") (pintype "passive"))
      (node (ref "IC2") (pin "16") (pinfunction "VCC_CPOUT_16") (pintype "power_in"))
      (node (ref "IC2") (pin "2") (pinfunction "VREG_4V5_2") (pintype "passive"))
      (node (ref "IC2") (pin "3") (pinfunction "VCC_VCO_CORE_3") (pintype "power_in"))
      (node (ref "IC2") (pin "32") (pinfunction "VCC_RFOUT_32") (pintype "power_in"))
    )
    (net (code "72") (name "VREG_DIG") (class "Default")
      (node (ref "C18") (pin "2") (pinfunction "2_2") (pintype "passive"))
      (node (ref "C20") (pin "2") (pinfunction "2_2") (pintype "passive"))
      (node (ref "IC2") (pin "26") (pinfunction "VDD_DSM_NDIV_26") (pintype "power_in"))
      (node (ref "IC2") (pin "27") (pinfunction "VREG_DIG_27") (pintype "passive"))
    )
    (net (code "73") (name "VREG_REF") (class "Default")
      (node (ref "C16") (pin "1") (pinfunction "1_1") (pintype "passive"))
      (node (ref "C19") (pin "1") (pinfunction "1_1") (pintype "passive"))
      (node (ref "IC2") (pin "17") (pinfunction "VDD_PFD_17") (pintype "power_in"))
      (node (ref "IC2") (pin "19") (pinfunction "VREG_REF_19") (pintype "passive"))
    )
    (net (code "74") (name "VREG_RF") (class "Default")
      (node (ref "C14") (pin "1") (pinfunction "1_1") (pintype "passive"))
      (node (ref "C15") (pin "1") (pinfunction "1_1") (pintype "passive"))
      (node (ref "IC2") (pin "29") (pinfunction "VREG_RF_29") (pintype "passive"))
    )
    (net (code "75") (name "VREG_VCO") (class "Default")
      (node (ref "C7") (pin "2") (pinfunction "2_2") (pintype "passive"))
      (node (ref "C8") (pin "1") (pinfunction "1_1") (pintype "passive"))
      (node (ref "C9") (pin "1") (pinfunction "1_1") (pintype "passive"))
      (node (ref "IC2") (pin "14") (pinfunction "VDD_CP_14") (pintype "power_in"))
      (node (ref "IC2") (pin "8") (pinfunction "VREG_VCO_8") (pintype "passive"))
    )
    (net (code "76") (name "unconnected-(JP2-Pad11)") (class "Default")
      (node (ref "JP2") (pin "11") (pinfunction "11_11") (pintype "passive"))
    )
    (net (code "77") (name "unconnected-(JP2-Pad12)") (class "Default")
      (node (ref "JP2") (pin "12") (pinfunction "12_12") (pintype "passive"))
    )
    (net (code "78") (name "unconnected-(JP2-Pad13)") (class "Default")
      (node (ref "JP2") (pin "13") (pinfunction "13_13") (pintype "passive"))
    )
    (net (code "79") (name "unconnected-(JP2-Pad14)") (class "Default")
      (node (ref "JP2") (pin "14") (pinfunction "14_14") (pintype "passive"))
    )
  )
)
